# A.net
KiCad netlist of a schematic drawn in Altium Designer
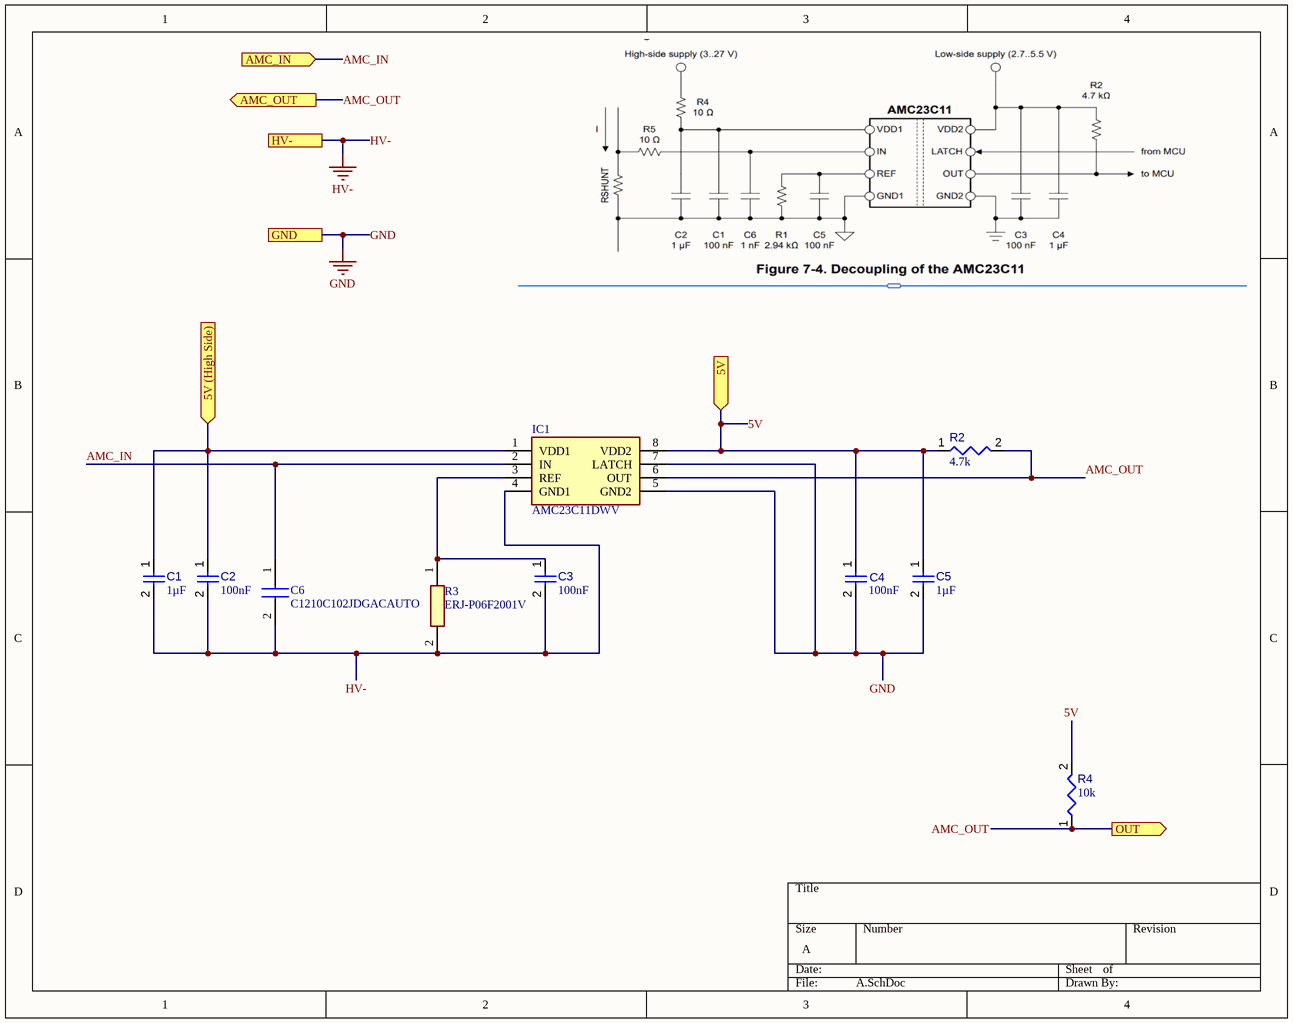
[diagram p0: A.SchDoc]

(export (version "E")
  (design (tool "Eeschema 10.0.6"))
  (components
    (comp (ref "C1")
      (value "1µF")
      (footprint "CAPC2013X135X45NL10T25")
      (description "Chip Capacitor, 1 uF, +/- 10%, 50 V, 0805 (2012 Metric)")
      (fields (field (name "TOLERANCE") "10%") (field (name "Comment") "Capacitor 1 uF +/- 10% 50 V 0805"))
      (libsource (lib "Hector Dela Rosa") (part "CAP-NP-2"))
    )
    (comp (ref "C2")
      (value "100nF")
      (footprint "CAPC2013X95X50LL10T25")
      (description "Chip Capacitor, 100 nF, +/- 10%, 50 V, 0805 (2012 Metric)")
      (fields (field (name "TOLERANCE") "10%") (field (name "Comment") "Capacitor 100 nF +/-10% 50 V 0805"))
      (libsource (lib "Hector Dela Rosa") (part "CAP-NP-2"))
    )
    (comp (ref "C3")
      (value "100nF")
      (footprint "CAPC2013X95X50LL10T25")
      (description "Chip Capacitor, 100 nF, +/- 10%, 50 V, 0805 (2012 Metric)")
      (fields (field (name "TOLERANCE") "10%") (field (name "Comment") "Capacitor 100 nF +/-10% 50 V 0805"))
      (libsource (lib "Hector Dela Rosa") (part "CAP-NP-2"))
    )
    (comp (ref "C4")
      (value "100nF")
      (footprint "CAPC2013X95X50LL10T25")
      (description "Chip Capacitor, 100 nF, +/- 10%, 50 V, 0805 (2012 Metric)")
      (fields (field (name "TOLERANCE") "10%") (field (name "Comment") "Capacitor 100 nF +/-10% 50 V 0805"))
      (libsource (lib "Hector Dela Rosa") (part "CAP-NP-2"))
    )
    (comp (ref "C5")
      (value "1µF")
      (footprint "CAPC2013X135X45NL10T25")
      (description "Chip Capacitor, 1 uF, +/- 10%, 50 V, 0805 (2012 Metric)")
      (fields (field (name "TOLERANCE") "10%") (field (name "Comment") "Capacitor 1 uF +/- 10% 50 V 0805"))
      (libsource (lib "Hector Dela Rosa") (part "CAP-NP-2"))
    )
    (comp (ref "C6")
      (value "C1210C102JDGACAUTO")
      (footprint "SamacSys:C1210")
      (description "Capacitor")
      (fields (field (name "MOUSER PART NUMBER") "80-C1210C102JDGAUTO"))
      (libsource (lib "*") (part "C1210C102JDGACAUTO"))
    )
    (comp (ref "IC1")
      (value "AMC23C11DWV")
      (footprint "SamacSys:SOIC127P1150X280-8N")
      (description "Integrated Circuit")
      (fields (field (name "MOUSER PART NUMBER") "595-AMC23C11DWV"))
      (libsource (lib "*") (part "AMC23C11DWV"))
    )
    (comp (ref "R2")
      (value "4.7k")
      (footprint "RESC2013X70X40ML20T20")
      (description "Chip Resistor, 4.7 KOhm, +/- 1%, 0.125 W, -55 to 155 degC, 0805 (2012 Metric)")
      (fields (field (name "POWER") "125mW") (field (name "TOLERANCE") "1%"))
      (libsource (lib "Hector Dela Rosa") (part "RES-2"))
    )
    (comp (ref "R3")
      (value "ERJ-P06F2001V")
      (footprint "SamacSys:ERJP06D1000V")
      (description "Resistor")
      (fields (field (name "MOUSER PART NUMBER") "667-ERJ-P06F2001V"))
      (libsource (lib "*") (part "ERJ-P06F2001V"))
    )
    (comp (ref "R4")
      (value "10k")
      (footprint "RESC2013X50X35ML15T15")
      (description "Chip Resistor, 10 KOhm, +/- 1%, 125 mW, -55 to 155 degC, 0805 (2012 Metric)")
      (fields (field (name "TOLERANCE") "1%") (field (name "POWER") "125mW"))
      (libsource (lib "Hector Dela Rosa") (part "RES-2"))
    )
  )
  (nets
    (net (code "1") (name "/5V") (class "Default")
      (node (ref "C4") (pin "1") (pinfunction "1_1") (pintype "passive"))
      (node (ref "C5") (pin "1") (pinfunction "1_1") (pintype "passive"))
      (node (ref "IC1") (pin "8") (pinfunction "VDD2_8") (pintype "passive"))
      (node (ref "R2") (pin "1") (pinfunction "1_1") (pintype "passive"))
      (node (ref "R4") (pin "2") (pinfunction "2_2") (pintype "passive"))
    )
    (net (code "2") (name "/5V (High Side)") (class "Default")
      (node (ref "C1") (pin "1") (pinfunction "1_1") (pintype "passive"))
      (node (ref "C2") (pin "1") (pinfunction "1_1") (pintype "passive"))
      (node (ref "IC1") (pin "1") (pinfunction "VDD1_1") (pintype "passive"))
    )
    (net (code "3") (name "/AMC_IN") (class "Default")
      (node (ref "C6") (pin "1") (pinfunction "1_1") (pintype "passive"))
      (node (ref "IC1") (pin "2") (pinfunction "IN_2") (pintype "passive"))
    )
    (net (code "4") (name "/AMC_OUT") (class "Default")
      (node (ref "IC1") (pin "6") (pinfunction "OUT_6") (pintype "passive"))
      (node (ref "R2") (pin "2") (pinfunction "2_2") (pintype "passive"))
      (node (ref "R4") (pin "1") (pinfunction "1_1") (pintype "passive"))
    )
    (net (code "5") (name "GND") (class "Default")
      (node (ref "C4") (pin "2") (pinfunction "2_2") (pintype "passive"))
      (node (ref "C5") (pin "2") (pinfunction "2_2") (pintype "passive"))
      (node (ref "IC1") (pin "5") (pinfunction "GND2_5") (pintype "passive"))
      (node (ref "IC1") (pin "7") (pinfunction "LATCH_7") (pintype "passive"))
    )
    (net (code "6") (name "HV-") (class "Default")
      (node (ref "C1") (pin "2") (pinfunction "2_2") (pintype "passive"))
      (node (ref "C2") (pin "2") (pinfunction "2_2") (pintype "passive"))
      (node (ref "C3") (pin "2") (pinfunction "2_2") (pintype "passive"))
      (node (ref "C6") (pin "2") (pinfunction "2_2") (pintype "passive"))
      (node (ref "IC1") (pin "4") (pinfunction "GND1_4") (pintype "passive"))
      (node (ref "R3") (pin "2") (pinfunction "2_2") (pintype "passive"))
    )
    (net (code "7") (name "Net-(IC1-REF)") (class "Default")
      (node (ref "C3") (pin "1") (pinfunction "1_1") (pintype "passive"))
      (node (ref "IC1") (pin "3") (pinfunction "REF_3") (pintype "passive"))
      (node (ref "R3") (pin "1") (pinfunction "1_1") (pintype "passive"))
    )
  )
)
